# MCU_POWER.net
KiCad netlist of a schematic drawn in Altium Designer
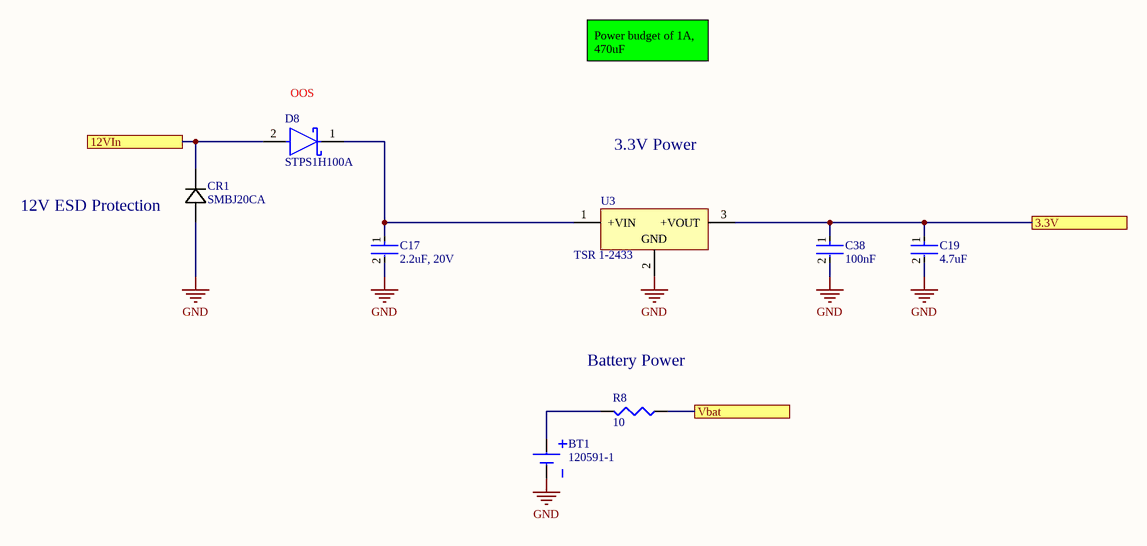
[diagram p0: MCU_POWER.SchDoc]

(export (version "E")
  (design (tool "Eeschema 10.0.6"))
  (components
    (comp (ref "BT1")
      (value "120591-1")
      (footprint "TECO-120591-1-2_V")
      (description "Lithium Battery Holder for CR2032 3V Cell")
      (fields (field (name "MANUFACTURER") "TE Connectivity"))
      (libsource (lib "Altium Content Vault") (part "TECO-120591-1-2"))
    )
    (comp (ref "C17")
      (value "2.2uF, 20V")
      (footprint "FP-C0603C-CF-MFG")
      (description "Any 0603 Cap is fine here")
      (fields (field (name "TOLERANCE") "0.1") (field (name "MANUFACTURER") "KEMET"))
      (libsource (lib "Altium Content Vault") (part "b4654b650e69147ec39a6b967a45e02"))
    )
    (comp (ref "C19")
      (value "4.7uF")
      (footprint "FP-C0603C-CF-MFG")
      (description "Any 0603 Cap is fine here")
      (fields (field (name "TOLERANCE") "0.1") (field (name "MANUFACTURER") "KEMET"))
      (libsource (lib "Altium Content Vault") (part "b4654b650e69147ec39a6b967a45e02"))
    )
    (comp (ref "C38")
      (value "100nF")
      (footprint "FP-C0603C-CF-MFG")
      (description "Any 0603 Cap is fine here")
      (fields (field (name "TOLERANCE") "0.1") (field (name "MANUFACTURER") "KEMET"))
      (libsource (lib "Altium Content Vault") (part "b4654b650e69147ec39a6b967a45e02"))
    )
    (comp (ref "CR1")
      (value "SMBJ20CA")
      (footprint "SMB")
      (description "Imported")
      (libsource (lib "Gopher-Motorsports-Library") (part "SMBJ20CA"))
    )
    (comp (ref "D8")
      (value "STPS1H100A")
      (footprint "FP-SMA-MFG")
      (description "DIODE SCHOTTKY 100V 1A SMA")
      (fields
        (field (name "MANUFACTURER") "STMicroelectronics")
        (field (name "OCTOPART") "https://octopart.com/stps1h100a-stmicroelectronics-55399361")
      )
      (libsource (lib "Altium Content Vault") (part "fefb30dabb5d097ae2f038500735429"))
    )
    (comp (ref "R8")
      (value "10")
      (footprint "J1-0603")
      (description "Resistor")
      (fields (field (name "PUBLISHER") "Altium Limited"))
      (libsource (lib "Miscellaneous Devices") (part "Res3"))
    )
    (comp (ref "U3")
      (value "TSR 1-2433")
      (footprint "TRACO-SIP-3_V")
      (description "DC/DC Converter, TSR-1 Series, 3.3 VDC, 1 A, -40 to 85 degC, 3-Pin THD (SIP), RoHS")
      (fields (field (name "MANUFACTURER") "Tracopower"))
      (libsource (lib "Altium Content Vault") (part "TRACO-TSR1-2433-SIP-3"))
    )
  )
  (nets
    (net (code "1") (name "/3.3V") (class "Default")
      (node (ref "C19") (pin "1") (pinfunction "1_1") (pintype "passive"))
      (node (ref "C38") (pin "1") (pinfunction "1_1") (pintype "passive"))
      (node (ref "U3") (pin "3") (pinfunction "+VOUT_3") (pintype "power_in"))
    )
    (net (code "2") (name "/12VIn") (class "Default")
      (node (ref "CR1") (pin "1") (pinfunction "1_1") (pintype "passive"))
      (node (ref "D8") (pin "2") (pinfunction "A_2") (pintype "passive"))
    )
    (net (code "3") (name "/Vbat") (class "Default")
      (node (ref "R8") (pin "1") (pinfunction "1_1") (pintype "passive"))
    )
    (net (code "4") (name "GND") (class "Default")
      (node (ref "BT1") (pin "2") (pinfunction "-_2") (pintype "passive"))
      (node (ref "C17") (pin "2") (pinfunction "2_2") (pintype "passive"))
      (node (ref "C19") (pin "2") (pinfunction "2_2") (pintype "passive"))
      (node (ref "C38") (pin "2") (pinfunction "2_2") (pintype "passive"))
      (node (ref "CR1") (pin "2") (pinfunction "2_2") (pintype "passive"))
      (node (ref "U3") (pin "2") (pinfunction "GND_2") (pintype "power_in"))
    )
    (net (code "5") (name "Net-(BT1-+)") (class "Default")
      (node (ref "BT1") (pin "1") (pinfunction "+_1") (pintype "passive"))
      (node (ref "R8") (pin "2") (pinfunction "2_2") (pintype "passive"))
    )
    (net (code "6") (name "Net-(D8-K)") (class "Default")
      (node (ref "C17") (pin "1") (pinfunction "1_1") (pintype "passive"))
      (node (ref "D8") (pin "1") (pinfunction "K_1") (pintype "passive"))
      (node (ref "U3") (pin "1") (pinfunction "+VIN_1") (pintype "power_in"))
    )
  )
)
